# felicia.net
KiCad netlist of a schematic drawn in EAGLE
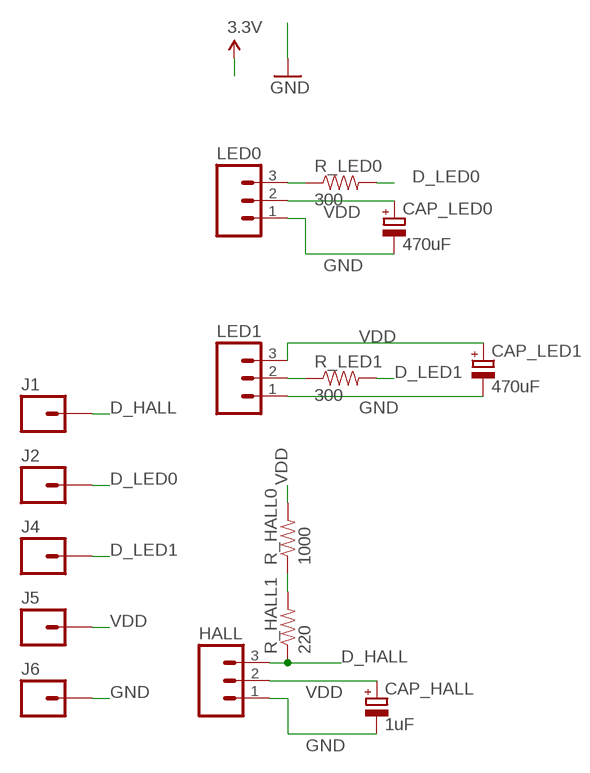
[diagram p0: schematic, sheet 1]

(export (version "E")
  (design (tool "Eeschema 10.0.6"))
  (components
    (comp (ref "CAP_HALL")
      (value "1uF")
      (footprint "eagle-import:E5-4")
      (libsource (lib "eagle-import") (part "CPOL-EUE5-4"))
    )
    (comp (ref "CAP_LED0")
      (value "470uF")
      (footprint "eagle-import:E3,5-8")
      (libsource (lib "eagle-import") (part "CPOL-EUE3.5-8"))
    )
    (comp (ref "CAP_LED1")
      (value "470uF")
      (footprint "eagle-import:E3,5-8")
      (libsource (lib "eagle-import") (part "CPOL-EUE3.5-8"))
    )
    (comp (ref "HALL")
      (value "M031X03_NO_SILK")
      (footprint "eagle-import:1X03_NO_SILK")
      (libsource (lib "eagle-import") (part "M031X03_NO_SILK"))
    )
    (comp (ref "J1")
      (value "M01NOSILK-KIT")
      (footprint "eagle-import:1X01NS-KIT")
      (libsource (lib "eagle-import") (part "M01NOSILK-KIT"))
    )
    (comp (ref "J2")
      (value "M01NOSILK-KIT")
      (footprint "eagle-import:1X01NS-KIT")
      (libsource (lib "eagle-import") (part "M01NOSILK-KIT"))
    )
    (comp (ref "J4")
      (value "M01NOSILK-KIT")
      (footprint "eagle-import:1X01NS-KIT")
      (libsource (lib "eagle-import") (part "M01NOSILK-KIT"))
    )
    (comp (ref "J5")
      (value "M01NOSILK-KIT")
      (footprint "eagle-import:1X01NS-KIT")
      (libsource (lib "eagle-import") (part "M01NOSILK-KIT"))
    )
    (comp (ref "J6")
      (value "M01NOSILK-KIT")
      (footprint "eagle-import:1X01NS-KIT")
      (libsource (lib "eagle-import") (part "M01NOSILK-KIT"))
    )
    (comp (ref "LED0")
      (value "M031X03_NO_SILK")
      (footprint "eagle-import:1X03_NO_SILK")
      (libsource (lib "eagle-import") (part "M031X03_NO_SILK"))
    )
    (comp (ref "LED1")
      (value "M031X03_NO_SILK")
      (footprint "eagle-import:1X03_NO_SILK")
      (libsource (lib "eagle-import") (part "M031X03_NO_SILK"))
    )
    (comp (ref "R_HALL0")
      (value "1000")
      (footprint "eagle-import:AXIAL-0.4")
      (libsource (lib "eagle-import") (part "RESISTORPTH-1/4W"))
    )
    (comp (ref "R_HALL1")
      (value "220")
      (footprint "eagle-import:AXIAL-0.4")
      (libsource (lib "eagle-import") (part "RESISTORPTH-1/4W"))
    )
    (comp (ref "R_LED0")
      (value "300")
      (footprint "eagle-import:AXIAL-0.4")
      (libsource (lib "eagle-import") (part "RESISTORPTH-1/4W"))
    )
    (comp (ref "R_LED1")
      (value "300")
      (footprint "eagle-import:AXIAL-0.4")
      (libsource (lib "eagle-import") (part "RESISTORPTH-1/4W"))
    )
  )
  (nets
    (net (code "1") (name "/D_HALL") (class "Default")
      (node (ref "HALL") (pin "3") (pinfunction "3_3") (pintype "passive"))
      (node (ref "J1") (pin "1") (pinfunction "1_1") (pintype "passive"))
      (node (ref "R_HALL1") (pin "P$1") (pinfunction "1_P$1") (pintype "passive"))
    )
    (net (code "2") (name "/D_LED0") (class "Default")
      (node (ref "J2") (pin "1") (pinfunction "1_1") (pintype "passive"))
      (node (ref "R_LED0") (pin "P$2") (pinfunction "2_P$2") (pintype "passive"))
    )
    (net (code "3") (name "/D_LED1") (class "Default")
      (node (ref "J4") (pin "1") (pinfunction "1_1") (pintype "passive"))
      (node (ref "R_LED1") (pin "P$2") (pinfunction "2_P$2") (pintype "passive"))
    )
    (net (code "4") (name "3.3V") (class "Default")
      (node (ref "CAP_HALL") (pin "+") (pinfunction "+_+") (pintype "passive"))
      (node (ref "CAP_LED0") (pin "+") (pinfunction "+_+") (pintype "passive"))
      (node (ref "CAP_LED1") (pin "+") (pinfunction "+_+") (pintype "passive"))
      (node (ref "HALL") (pin "2") (pinfunction "2_2") (pintype "passive"))
      (node (ref "J5") (pin "1") (pinfunction "1_1") (pintype "passive"))
      (node (ref "LED0") (pin "2") (pinfunction "2_2") (pintype "passive"))
      (node (ref "LED1") (pin "3") (pinfunction "3_3") (pintype "passive"))
      (node (ref "R_HALL0") (pin "P$2") (pinfunction "2_P$2") (pintype "passive"))
    )
    (net (code "5") (name "GND") (class "Default")
      (node (ref "CAP_HALL") (pin "-") (pinfunction "-_-") (pintype "passive"))
      (node (ref "CAP_LED0") (pin "-") (pinfunction "-_-") (pintype "passive"))
      (node (ref "CAP_LED1") (pin "-") (pinfunction "-_-") (pintype "passive"))
      (node (ref "HALL") (pin "1") (pinfunction "1_1") (pintype "passive"))
      (node (ref "J6") (pin "1") (pinfunction "1_1") (pintype "passive"))
      (node (ref "LED0") (pin "1") (pinfunction "1_1") (pintype "passive"))
      (node (ref "LED1") (pin "1") (pinfunction "1_1") (pintype "passive"))
    )
    (net (code "6") (name "Net-(R_HALL0-1)") (class "Default")
      (node (ref "R_HALL0") (pin "P$1") (pinfunction "1_P$1") (pintype "passive"))
      (node (ref "R_HALL1") (pin "P$2") (pinfunction "2_P$2") (pintype "passive"))
    )
    (net (code "7") (name "Net-(R_LED0-1)") (class "Default")
      (node (ref "LED0") (pin "3") (pinfunction "3_3") (pintype "passive"))
      (node (ref "R_LED0") (pin "P$1") (pinfunction "1_P$1") (pintype "passive"))
    )
    (net (code "8") (name "Net-(R_LED1-1)") (class "Default")
      (node (ref "LED1") (pin "2") (pinfunction "2_2") (pintype "passive"))
      (node (ref "R_LED1") (pin "P$1") (pinfunction "1_P$1") (pintype "passive"))
    )
  )
)
